# CPLD.net
KiCad netlist of a schematic drawn in Altium Designer
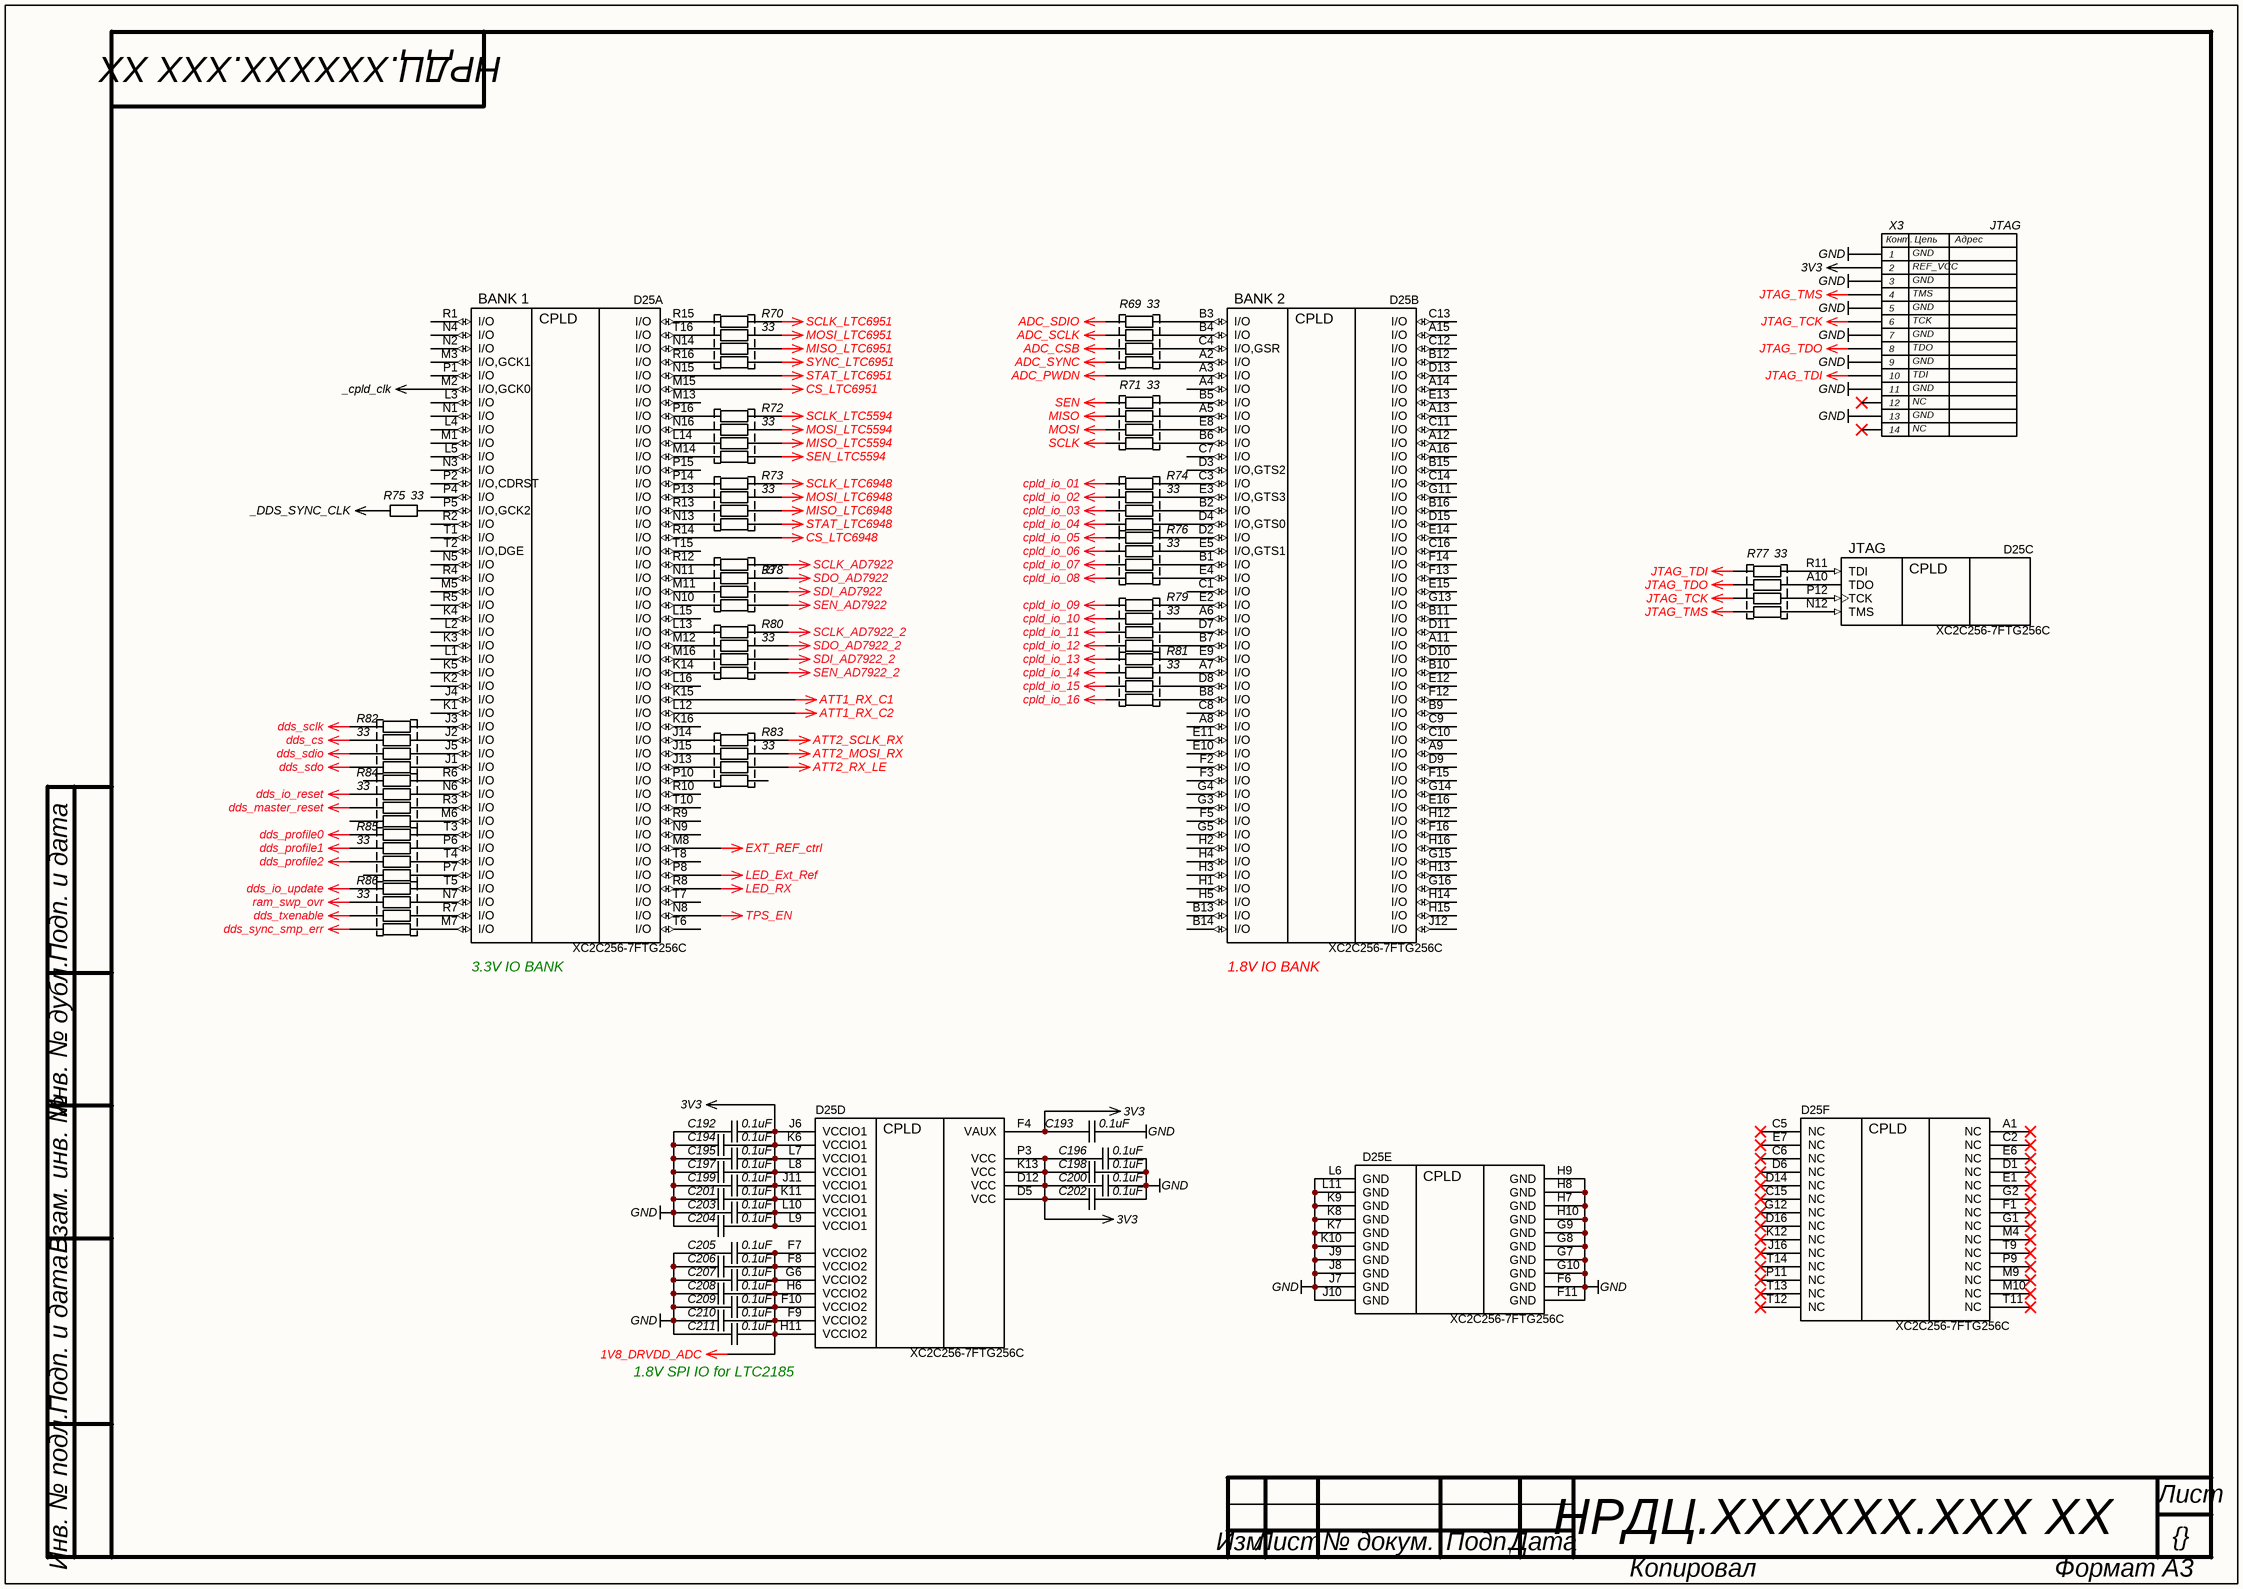
[diagram p0: CPLD.SchDoc]

(export (version "E")
  (design (tool "Eeschema 10.0.6"))
  (components
    (comp (ref "C192")
      (value "0.1uF")
      (footprint "C0402")
      (description "SMD Capacitor")
      (fields (field (name "MANUFACTURER") "Murata") (field (name "TOLERANCE") "10%"))
      (libsource (lib "Kintex_SDR") (part "CAP"))
    )
    (comp (ref "C193")
      (value "0.1uF")
      (footprint "C0402")
      (description "SMD Capacitor")
      (fields (field (name "MANUFACTURER") "Murata") (field (name "TOLERANCE") "10%"))
      (libsource (lib "Kintex_SDR") (part "CAP"))
    )
    (comp (ref "C194")
      (value "0.1uF")
      (footprint "C0402")
      (description "SMD Capacitor")
      (fields (field (name "MANUFACTURER") "Murata") (field (name "TOLERANCE") "10%"))
      (libsource (lib "Kintex_SDR") (part "CAP"))
    )
    (comp (ref "C195")
      (value "0.1uF")
      (footprint "C0402")
      (description "SMD Capacitor")
      (fields (field (name "MANUFACTURER") "Murata") (field (name "TOLERANCE") "10%"))
      (libsource (lib "Kintex_SDR") (part "CAP"))
    )
    (comp (ref "C196")
      (value "0.1uF")
      (footprint "C0402")
      (description "SMD Capacitor")
      (fields (field (name "MANUFACTURER") "Murata") (field (name "TOLERANCE") "10%"))
      (libsource (lib "Kintex_SDR") (part "CAP"))
    )
    (comp (ref "C197")
      (value "0.1uF")
      (footprint "C0402")
      (description "SMD Capacitor")
      (fields (field (name "MANUFACTURER") "Murata") (field (name "TOLERANCE") "10%"))
      (libsource (lib "Kintex_SDR") (part "CAP"))
    )
    (comp (ref "C198")
      (value "0.1uF")
      (footprint "C0402")
      (description "SMD Capacitor")
      (fields (field (name "MANUFACTURER") "Murata") (field (name "TOLERANCE") "10%"))
      (libsource (lib "Kintex_SDR") (part "CAP"))
    )
    (comp (ref "C199")
      (value "0.1uF")
      (footprint "C0402")
      (description "SMD Capacitor")
      (fields (field (name "MANUFACTURER") "Murata") (field (name "TOLERANCE") "10%"))
      (libsource (lib "Kintex_SDR") (part "CAP"))
    )
    (comp (ref "C200")
      (value "0.1uF")
      (footprint "C0402")
      (description "SMD Capacitor")
      (fields (field (name "MANUFACTURER") "Murata") (field (name "TOLERANCE") "10%"))
      (libsource (lib "Kintex_SDR") (part "CAP"))
    )
    (comp (ref "C201")
      (value "0.1uF")
      (footprint "C0402")
      (description "SMD Capacitor")
      (fields (field (name "MANUFACTURER") "Murata") (field (name "TOLERANCE") "10%"))
      (libsource (lib "Kintex_SDR") (part "CAP"))
    )
    (comp (ref "C202")
      (value "0.1uF")
      (footprint "C0402")
      (description "SMD Capacitor")
      (fields (field (name "MANUFACTURER") "Murata") (field (name "TOLERANCE") "10%"))
      (libsource (lib "Kintex_SDR") (part "CAP"))
    )
    (comp (ref "C203")
      (value "0.1uF")
      (footprint "C0402")
      (description "SMD Capacitor")
      (fields (field (name "MANUFACTURER") "Murata") (field (name "TOLERANCE") "10%"))
      (libsource (lib "Kintex_SDR") (part "CAP"))
    )
    (comp (ref "C204")
      (value "0.1uF")
      (footprint "C0402")
      (description "SMD Capacitor")
      (fields (field (name "MANUFACTURER") "Murata") (field (name "TOLERANCE") "10%"))
      (libsource (lib "Kintex_SDR") (part "CAP"))
    )
    (comp (ref "C205")
      (value "0.1uF")
      (footprint "C0402")
      (description "SMD Capacitor")
      (fields (field (name "MANUFACTURER") "Murata") (field (name "TOLERANCE") "10%"))
      (libsource (lib "Kintex_SDR") (part "CAP"))
    )
    (comp (ref "C206")
      (value "0.1uF")
      (footprint "C0402")
      (description "SMD Capacitor")
      (fields (field (name "MANUFACTURER") "Murata") (field (name "TOLERANCE") "10%"))
      (libsource (lib "Kintex_SDR") (part "CAP"))
    )
    (comp (ref "C207")
      (value "0.1uF")
      (footprint "C0402")
      (description "SMD Capacitor")
      (fields (field (name "MANUFACTURER") "Murata") (field (name "TOLERANCE") "10%"))
      (libsource (lib "Kintex_SDR") (part "CAP"))
    )
    (comp (ref "C208")
      (value "0.1uF")
      (footprint "C0402")
      (description "SMD Capacitor")
      (fields (field (name "MANUFACTURER") "Murata") (field (name "TOLERANCE") "10%"))
      (libsource (lib "Kintex_SDR") (part "CAP"))
    )
    (comp (ref "C209")
      (value "0.1uF")
      (footprint "C0402")
      (description "SMD Capacitor")
      (fields (field (name "MANUFACTURER") "Murata") (field (name "TOLERANCE") "10%"))
      (libsource (lib "Kintex_SDR") (part "CAP"))
    )
    (comp (ref "C210")
      (value "0.1uF")
      (footprint "C0402")
      (description "SMD Capacitor")
      (fields (field (name "MANUFACTURER") "Murata") (field (name "TOLERANCE") "10%"))
      (libsource (lib "Kintex_SDR") (part "CAP"))
    )
    (comp (ref "C211")
      (value "0.1uF")
      (footprint "C0402")
      (description "SMD Capacitor")
      (fields (field (name "MANUFACTURER") "Murata") (field (name "TOLERANCE") "10%"))
      (libsource (lib "Kintex_SDR") (part "CAP"))
    )
    (comp (ref "D25")
      (value "XC2C256-7FTG256C")
      (footprint "DBLib:FTG256")
      (description "CoolRunner-II 1.8V, 256 Macrocell CPLD, 184 User I/Os, 256-Ball FTBGA, Commercial Grade, Pb-Free")
      (libsource (lib "DBLib") (part "XC2C256-7FTG256C"))
    )
    (comp (ref "R69")
      (value "33")
      (footprint "EXN8V")
      (description "Chip Resistor Array")
      (fields (field (name "TOLERANCE") "5%") (field (name "MANUFACTURER") "Panasonic"))
      (libsource (lib "Kintex_SDR") (part "RES 4x0402"))
    )
    (comp (ref "R70")
      (value "33")
      (footprint "EXN8V")
      (description "Chip Resistor Array")
      (fields (field (name "TOLERANCE") "5%") (field (name "MANUFACTURER") "Panasonic"))
      (libsource (lib "Kintex_SDR") (part "RES 4x0402"))
    )
    (comp (ref "R71")
      (value "33")
      (footprint "EXN8V")
      (description "Chip Resistor Array")
      (fields (field (name "TOLERANCE") "5%") (field (name "MANUFACTURER") "Panasonic"))
      (libsource (lib "Kintex_SDR") (part "RES 4x0402"))
    )
    (comp (ref "R72")
      (value "33")
      (footprint "EXN8V")
      (description "Chip Resistor Array")
      (fields (field (name "TOLERANCE") "5%") (field (name "MANUFACTURER") "Panasonic"))
      (libsource (lib "Kintex_SDR") (part "RES 4x0402"))
    )
    (comp (ref "R73")
      (value "33")
      (footprint "EXN8V")
      (description "Chip Resistor Array")
      (fields (field (name "TOLERANCE") "5%") (field (name "MANUFACTURER") "Panasonic"))
      (libsource (lib "Kintex_SDR") (part "RES 4x0402"))
    )
    (comp (ref "R74")
      (value "33")
      (footprint "EXN8V")
      (description "Chip Resistor Array")
      (fields (field (name "TOLERANCE") "5%") (field (name "MANUFACTURER") "Panasonic"))
      (libsource (lib "Kintex_SDR") (part "RES 4x0402"))
    )
    (comp (ref "R75")
      (value "33")
      (footprint "R0402")
      (description "SMD Resistor")
      (fields (field (name "POWER") "0.062 Wt") (field (name "TOLERANCE") "5%"))
      (libsource (lib "Kintex_SDR") (part "RES"))
    )
    (comp (ref "R76")
      (value "33")
      (footprint "EXN8V")
      (description "Chip Resistor Array")
      (fields (field (name "TOLERANCE") "5%") (field (name "MANUFACTURER") "Panasonic"))
      (libsource (lib "Kintex_SDR") (part "RES 4x0402"))
    )
    (comp (ref "R77")
      (value "33")
      (footprint "EXN8V")
      (description "Chip Resistor Array")
      (fields (field (name "TOLERANCE") "5%") (field (name "MANUFACTURER") "Panasonic"))
      (libsource (lib "Kintex_SDR") (part "RES 4x0402"))
    )
    (comp (ref "R78")
      (value "33")
      (footprint "EXN8V")
      (description "Chip Resistor Array")
      (fields (field (name "TOLERANCE") "5%") (field (name "MANUFACTURER") "Panasonic"))
      (libsource (lib "Kintex_SDR") (part "RES 4x0402"))
    )
    (comp (ref "R79")
      (value "33")
      (footprint "EXN8V")
      (description "Chip Resistor Array")
      (fields (field (name "TOLERANCE") "5%") (field (name "MANUFACTURER") "Panasonic"))
      (libsource (lib "Kintex_SDR") (part "RES 4x0402"))
    )
    (comp (ref "R80")
      (value "33")
      (footprint "EXN8V")
      (description "Chip Resistor Array")
      (fields (field (name "TOLERANCE") "5%") (field (name "MANUFACTURER") "Panasonic"))
      (libsource (lib "Kintex_SDR") (part "RES 4x0402"))
    )
    (comp (ref "R81")
      (value "33")
      (footprint "EXN8V")
      (description "Chip Resistor Array")
      (fields (field (name "TOLERANCE") "5%") (field (name "MANUFACTURER") "Panasonic"))
      (libsource (lib "Kintex_SDR") (part "RES 4x0402"))
    )
    (comp (ref "R82")
      (value "33")
      (footprint "EXN8V")
      (description "Chip Resistor Array")
      (fields (field (name "TOLERANCE") "5%") (field (name "MANUFACTURER") "Panasonic"))
      (libsource (lib "Kintex_SDR") (part "RES 4x0402"))
    )
    (comp (ref "R83")
      (value "33")
      (footprint "EXN8V")
      (description "Chip Resistor Array")
      (fields (field (name "TOLERANCE") "5%") (field (name "MANUFACTURER") "Panasonic"))
      (libsource (lib "Kintex_SDR") (part "RES 4x0402"))
    )
    (comp (ref "R84")
      (value "33")
      (footprint "EXN8V")
      (description "Chip Resistor Array")
      (fields (field (name "TOLERANCE") "5%") (field (name "MANUFACTURER") "Panasonic"))
      (libsource (lib "Kintex_SDR") (part "RES 4x0402"))
    )
    (comp (ref "R85")
      (value "33")
      (footprint "EXN8V")
      (description "Chip Resistor Array")
      (fields (field (name "TOLERANCE") "5%") (field (name "MANUFACTURER") "Panasonic"))
      (libsource (lib "Kintex_SDR") (part "RES 4x0402"))
    )
    (comp (ref "R86")
      (value "33")
      (footprint "EXN8V")
      (description "Chip Resistor Array")
      (fields (field (name "TOLERANCE") "5%") (field (name "MANUFACTURER") "Panasonic"))
      (libsource (lib "Kintex_SDR") (part "RES 4x0402"))
    )
    (comp (ref "X3")
      (value "JTAG")
      (footprint "DBLib:JTAG Mail 2mm")
      (description "2.00mm Pitch, Milli-Grid PCB Header, Dual Row, Vertical, Through Hole, Shrouded, 14\r\nCircuits")
      (fields (field (name "MANUFACTURER") "Molex"))
      (libsource (lib "DBLib") (part "HDR Debug_14-pin"))
    )
  )
  (nets
    (net (code "1") (name "1V8_DRVDD_ADC") (class "Default")
      (node (ref "C205") (pin "2") (pinfunction "2_2") (pintype "passive"))
      (node (ref "C206") (pin "2") (pinfunction "2_2") (pintype "passive"))
      (node (ref "C207") (pin "2") (pinfunction "2_2") (pintype "passive"))
      (node (ref "C208") (pin "2") (pinfunction "2_2") (pintype "passive"))
      (node (ref "C209") (pin "2") (pinfunction "2_2") (pintype "passive"))
      (node (ref "C210") (pin "2") (pinfunction "2_2") (pintype "passive"))
      (node (ref "C211") (pin "2") (pinfunction "2_2") (pintype "passive"))
      (node (ref "D25") (pin "F10") (pinfunction "VCCIO2_F10") (pintype "power_in"))
      (node (ref "D25") (pin "F7") (pinfunction "VCCIO2_F7") (pintype "power_in"))
      (node (ref "D25") (pin "F8") (pinfunction "VCCIO2_F8") (pintype "power_in"))
      (node (ref "D25") (pin "F9") (pinfunction "VCCIO2_F9") (pintype "power_in"))
      (node (ref "D25") (pin "G6") (pinfunction "VCCIO2_G6") (pintype "power_in"))
      (node (ref "D25") (pin "H11") (pinfunction "VCCIO2_H11") (pintype "power_in"))
      (node (ref "D25") (pin "H6") (pinfunction "VCCIO2_H6") (pintype "power_in"))
    )
    (net (code "2") (name "3V3") (class "Default")
      (node (ref "C192") (pin "2") (pinfunction "2_2") (pintype "passive"))
      (node (ref "C193") (pin "1") (pinfunction "1_1") (pintype "passive"))
      (node (ref "C194") (pin "2") (pinfunction "2_2") (pintype "passive"))
      (node (ref "C195") (pin "2") (pinfunction "2_2") (pintype "passive"))
      (node (ref "C196") (pin "1") (pinfunction "1_1") (pintype "passive"))
      (node (ref "C197") (pin "2") (pinfunction "2_2") (pintype "passive"))
      (node (ref "C198") (pin "1") (pinfunction "1_1") (pintype "passive"))
      (node (ref "C199") (pin "2") (pinfunction "2_2") (pintype "passive"))
      (node (ref "C200") (pin "1") (pinfunction "1_1") (pintype "passive"))
      (node (ref "C201") (pin "2") (pinfunction "2_2") (pintype "passive"))
      (node (ref "C202") (pin "1") (pinfunction "1_1") (pintype "passive"))
      (node (ref "C203") (pin "2") (pinfunction "2_2") (pintype "passive"))
      (node (ref "C204") (pin "2") (pinfunction "2_2") (pintype "passive"))
      (node (ref "D25") (pin "D12") (pinfunction "VCC_D12") (pintype "power_in"))
      (node (ref "D25") (pin "D5") (pinfunction "VCC_D5") (pintype "power_in"))
      (node (ref "D25") (pin "F4") (pinfunction "VAUX_F4") (pintype "power_in"))
      (node (ref "D25") (pin "J11") (pinfunction "VCCIO1_J11") (pintype "power_in"))
      (node (ref "D25") (pin "J6") (pinfunction "VCCIO1_J6") (pintype "power_in"))
      (node (ref "D25") (pin "K11") (pinfunction "VCCIO1_K11") (pintype "power_in"))
      (node (ref "D25") (pin "K13") (pinfunction "VCC_K13") (pintype "power_in"))
      (node (ref "D25") (pin "K6") (pinfunction "VCCIO1_K6") (pintype "power_in"))
      (node (ref "D25") (pin "L10") (pinfunction "VCCIO1_L10") (pintype "power_in"))
      (node (ref "D25") (pin "L7") (pinfunction "VCCIO1_L7") (pintype "power_in"))
      (node (ref "D25") (pin "L8") (pinfunction "VCCIO1_L8") (pintype "power_in"))
      (node (ref "D25") (pin "L9") (pinfunction "VCCIO1_L9") (pintype "power_in"))
      (node (ref "D25") (pin "P3") (pinfunction "VCC_P3") (pintype "power_in"))
      (node (ref "X3") (pin "2") (pinfunction "2_2") (pintype "passive"))
    )
    (net (code "3") (name "ADC_CSB") (class "Default")
      (node (ref "R69") (pin "7") (pinfunction "7_7") (pintype "passive"))
    )
    (net (code "4") (name "ADC_PWDN") (class "Default")
      (node (ref "D25") (pin "A3") (pinfunction "I/O_A3") (pintype "bidirectional"))
    )
    (net (code "5") (name "ADC_SCLK") (class "Default")
      (node (ref "R69") (pin "6") (pinfunction "6_6") (pintype "passive"))
    )
    (net (code "6") (name "ADC_SDIO") (class "Default")
      (node (ref "R69") (pin "5") (pinfunction "5_5") (pintype "passive"))
    )
    (net (code "7") (name "ADC_SYNC") (class "Default")
      (node (ref "R69") (pin "8") (pinfunction "8_8") (pintype "passive"))
    )
    (net (code "8") (name "ATT1_RX_C1") (class "Default")
      (node (ref "D25") (pin "K15") (pinfunction "I/O_K15") (pintype "bidirectional"))
    )
    (net (code "9") (name "ATT1_RX_C2") (class "Default")
      (node (ref "D25") (pin "L12") (pinfunction "I/O_L12") (pintype "bidirectional"))
    )
    (net (code "10") (name "ATT2_MOSI_RX") (class "Default")
      (node (ref "R83") (pin "3") (pinfunction "3_3") (pintype "passive"))
    )
    (net (code "11") (name "ATT2_RX_LE") (class "Default")
      (node (ref "R83") (pin "2") (pinfunction "2_2") (pintype "passive"))
    )
    (net (code "12") (name "ATT2_SCLK_RX") (class "Default")
      (node (ref "R83") (pin "4") (pinfunction "4_4") (pintype "passive"))
    )
    (net (code "13") (name "CS_LTC6948") (class "Default")
      (node (ref "D25") (pin "R14") (pinfunction "I/O_R14") (pintype "bidirectional"))
    )
    (net (code "14") (name "CS_LTC6951") (class "Default")
      (node (ref "D25") (pin "M15") (pinfunction "I/O_M15") (pintype "bidirectional"))
    )
    (net (code "15") (name "EXT_REF_ctrl") (class "Default")
      (node (ref "D25") (pin "M8") (pinfunction "I/O_M8") (pintype "bidirectional"))
    )
    (net (code "16") (name "GND") (class "Default")
      (node (ref "C192") (pin "1") (pinfunction "1_1") (pintype "passive"))
      (node (ref "C193") (pin "2") (pinfunction "2_2") (pintype "passive"))
      (node (ref "C194") (pin "1") (pinfunction "1_1") (pintype "passive"))
      (node (ref "C195") (pin "1") (pinfunction "1_1") (pintype "passive"))
      (node (ref "C196") (pin "2") (pinfunction "2_2") (pintype "passive"))
      (node (ref "C197") (pin "1") (pinfunction "1_1") (pintype "passive"))
      (node (ref "C198") (pin "2") (pinfunction "2_2") (pintype "passive"))
      (node (ref "C199") (pin "1") (pinfunction "1_1") (pintype "passive"))
      (node (ref "C200") (pin "2") (pinfunction "2_2") (pintype "passive"))
      (node (ref "C201") (pin "1") (pinfunction "1_1") (pintype "passive"))
      (node (ref "C202") (pin "2") (pinfunction "2_2") (pintype "passive"))
      (node (ref "C203") (pin "1") (pinfunction "1_1") (pintype "passive"))
      (node (ref "C204") (pin "1") (pinfunction "1_1") (pintype "passive"))
      (node (ref "C205") (pin "1") (pinfunction "1_1") (pintype "passive"))
      (node (ref "C206") (pin "1") (pinfunction "1_1") (pintype "passive"))
      (node (ref "C207") (pin "1") (pinfunction "1_1") (pintype "passive"))
      (node (ref "C208") (pin "1") (pinfunction "1_1") (pintype "passive"))
      (node (ref "C209") (pin "1") (pinfunction "1_1") (pintype "passive"))
      (node (ref "C210") (pin "1") (pinfunction "1_1") (pintype "passive"))
      (node (ref "C211") (pin "1") (pinfunction "1_1") (pintype "passive"))
      (node (ref "D25") (pin "F11") (pinfunction "GND_F11") (pintype "power_in"))
      (node (ref "D25") (pin "F6") (pinfunction "GND_F6") (pintype "power_in"))
      (node (ref "D25") (pin "G10") (pinfunction "GND_G10") (pintype "power_in"))
      (node (ref "D25") (pin "G7") (pinfunction "GND_G7") (pintype "power_in"))
      (node (ref "D25") (pin "G8") (pinfunction "GND_G8") (pintype "power_in"))
      (node (ref "D25") (pin "G9") (pinfunction "GND_G9") (pintype "power_in"))
      (node (ref "D25") (pin "H10") (pinfunction "GND_H10") (pintype "power_in"))
      (node (ref "D25") (pin "H7") (pinfunction "GND_H7") (pintype "power_in"))
      (node (ref "D25") (pin "H8") (pinfunction "GND_H8") (pintype "power_in"))
      (node (ref "D25") (pin "H9") (pinfunction "GND_H9") (pintype "power_in"))
      (node (ref "D25") (pin "J10") (pinfunction "GND_J10") (pintype "power_in"))
      (node (ref "D25") (pin "J7") (pinfunction "GND_J7") (pintype "power_in"))
      (node (ref "D25") (pin "J8") (pinfunction "GND_J8") (pintype "power_in"))
      (node (ref "D25") (pin "J9") (pinfunction "GND_J9") (pintype "power_in"))
      (node (ref "D25") (pin "K10") (pinfunction "GND_K10") (pintype "power_in"))
      (node (ref "D25") (pin "K7") (pinfunction "GND_K7") (pintype "power_in"))
      (node (ref "D25") (pin "K8") (pinfunction "GND_K8") (pintype "power_in"))
      (node (ref "D25") (pin "K9") (pinfunction "GND_K9") (pintype "power_in"))
      (node (ref "D25") (pin "L11") (pinfunction "GND_L11") (pintype "power_in"))
      (node (ref "D25") (pin "L6") (pinfunction "GND_L6") (pintype "power_in"))
      (node (ref "X3") (pin "1") (pinfunction "1_1") (pintype "passive"))
      (node (ref "X3") (pin "11") (pinfunction "11_11") (pintype "passive"))
      (node (ref "X3") (pin "13") (pinfunction "13_13") (pintype "passive"))
      (node (ref "X3") (pin "3") (pinfunction "3_3") (pintype "passive"))
      (node (ref "X3") (pin "5") (pinfunction "5_5") (pintype "passive"))
      (node (ref "X3") (pin "7") (pinfunction "7_7") (pintype "passive"))
      (node (ref "X3") (pin "9") (pinfunction "9_9") (pintype "passive"))
    )
    (net (code "17") (name "JTAG_TCK") (class "Default")
      (node (ref "R77") (pin "7") (pinfunction "7_7") (pintype "passive"))
      (node (ref "X3") (pin "6") (pinfunction "6_6") (pintype "passive"))
    )
    (net (code "18") (name "JTAG_TDI") (class "Default")
      (node (ref "R77") (pin "5") (pinfunction "5_5") (pintype "passive"))
      (node (ref "X3") (pin "10") (pinfunction "10_10") (pintype "passive"))
    )
    (net (code "19") (name "JTAG_TDO") (class "Default")
      (node (ref "R77") (pin "6") (pinfunction "6_6") (pintype "passive"))
      (node (ref "X3") (pin "8") (pinfunction "8_8") (pintype "passive"))
    )
    (net (code "20") (name "JTAG_TMS") (class "Default")
      (node (ref "R77") (pin "8") (pinfunction "8_8") (pintype "passive"))
      (node (ref "X3") (pin "4") (pinfunction "4_4") (pintype "passive"))
    )
    (net (code "21") (name "LED_Ext_Ref") (class "Default")
      (node (ref "D25") (pin "P8") (pinfunction "I/O_P8") (pintype "bidirectional"))
    )
    (net (code "22") (name "LED_RX") (class "Default")
      (node (ref "D25") (pin "R8") (pinfunction "I/O_R8") (pintype "bidirectional"))
    )
    (net (code "23") (name "MISO") (class "Default")
      (node (ref "R71") (pin "6") (pinfunction "6_6") (pintype "passive"))
    )
    (net (code "24") (name "MISO_LTC5594") (class "Default")
      (node (ref "R72") (pin "2") (pinfunction "2_2") (pintype "passive"))
    )
    (net (code "25") (name "MISO_LTC6948") (class "Default")
      (node (ref "R73") (pin "2") (pinfunction "2_2") (pintype "passive"))
    )
    (net (code "26") (name "MISO_LTC6951") (class "Default")
      (node (ref "R70") (pin "2") (pinfunction "2_2") (pintype "passive"))
    )
    (net (code "27") (name "MOSI") (class "Default")
      (node (ref "R71") (pin "7") (pinfunction "7_7") (pintype "passive"))
    )
    (net (code "28") (name "MOSI_LTC5594") (class "Default")
      (node (ref "R72") (pin "3") (pinfunction "3_3") (pintype "passive"))
    )
    (net (code "29") (name "MOSI_LTC6948") (class "Default")
      (node (ref "R73") (pin "3") (pinfunction "3_3") (pintype "passive"))
    )
    (net (code "30") (name "MOSI_LTC6951") (class "Default")
      (node (ref "R70") (pin "3") (pinfunction "3_3") (pintype "passive"))
    )
    (net (code "31") (name "Net-(D25A-I{slash}O,GCK2)") (class "Default")
      (node (ref "D25") (pin "P5") (pinfunction "I/O,GCK2_P5") (pintype "bidirectional"))
      (node (ref "R75") (pin "2") (pinfunction "2_2") (pintype "passive"))
    )
    (net (code "32") (name "Net-(D25A-I{slash}O-PadJ1)") (class "Default")
      (node (ref "D25") (pin "J1") (pinfunction "I/O_J1") (pintype "bidirectional"))
      (node (ref "R82") (pin "1") (pinfunction "1_1") (pintype "passive"))
    )
    (net (code "33") (name "Net-(D25A-I{slash}O-PadJ2)") (class "Default")
      (node (ref "D25") (pin "J2") (pinfunction "I/O_J2") (pintype "bidirectional"))
      (node (ref "R82") (pin "3") (pinfunction "3_3") (pintype "passive"))
    )
    (net (code "34") (name "Net-(D25A-I{slash}O-PadJ3)") (class "Default")
      (node (ref "D25") (pin "J3") (pinfunction "I/O_J3") (pintype "bidirectional"))
      (node (ref "R82") (pin "4") (pinfunction "4_4") (pintype "passive"))
    )
    (net (code "35") (name "Net-(D25A-I{slash}O-PadJ5)") (class "Default")
      (node (ref "D25") (pin "J5") (pinfunction "I/O_J5") (pintype "bidirectional"))
      (node (ref "R82") (pin "2") (pinfunction "2_2") (pintype "passive"))
    )
    (net (code "36") (name "Net-(D25A-I{slash}O-PadJ13)") (class "Default")
      (node (ref "D25") (pin "J13") (pinfunction "I/O_J13") (pintype "bidirectional"))
      (node (ref "R83") (pin "7") (pinfunction "7_7") (pintype "passive"))
    )
    (net (code "37") (name "Net-(D25A-I{slash}O-PadJ14)") (class "Default")
      (node (ref "D25") (pin "J14") (pinfunction "I/O_J14") (pintype "bidirectional"))
      (node (ref "R83") (pin "5") (pinfunction "5_5") (pintype "passive"))
    )
    (net (code "38") (name "Net-(D25A-I{slash}O-PadJ15)") (class "Default")
      (node (ref "D25") (pin "J15") (pinfunction "I/O_J15") (pintype "bidirectional"))
      (node (ref "R83") (pin "6") (pinfunction "6_6") (pintype "passive"))
    )
    (net (code "39") (name "Net-(D25A-I{slash}O-PadK14)") (class "Default")
      (node (ref "D25") (pin "K14") (pinfunction "I/O_K14") (pintype "bidirectional"))
      (node (ref "R80") (pin "8") (pinfunction "8_8") (pintype "passive"))
    )
    (net (code "40") (name "Net-(D25A-I{slash}O-PadL13)") (class "Default")
      (node (ref "D25") (pin "L13") (pinfunction "I/O_L13") (pintype "bidirectional"))
      (node (ref "R80") (pin "5") (pinfunction "5_5") (pintype "passive"))
    )
    (net (code "41") (name "Net-(D25A-I{slash}O-PadL14)") (class "Default")
      (node (ref "D25") (pin "L14") (pinfunction "I/O_L14") (pintype "bidirectional"))
      (node (ref "R72") (pin "7") (pinfunction "7_7") (pintype "passive"))
    )
    (net (code "42") (name "Net-(D25A-I{slash}O-PadM6)") (class "Default")
      (node (ref "D25") (pin "M6") (pinfunction "I/O_M6") (pintype "bidirectional"))
      (node (ref "R84") (pin "1") (pinfunction "1_1") (pintype "passive"))
    )
    (net (code "43") (name "Net-(D25A-I{slash}O-PadM7)") (class "Default")
      (node (ref "D25") (pin "M7") (pinfunction "I/O_M7") (pintype "bidirectional"))
      (node (ref "R86") (pin "1") (pinfunction "1_1") (pintype "passive"))
    )
    (net (code "44") (name "Net-(D25A-I{slash}O-PadM11)") (class "Default")
      (node (ref "D25") (pin "M11") (pinfunction "I/O_M11") (pintype "bidirectional"))
      (node (ref "R78") (pin "7") (pinfunction "7_7") (pintype "passive"))
    )
    (net (code "45") (name "Net-(D25A-I{slash}O-PadM12)") (class "Default")
      (node (ref "D25") (pin "M12") (pinfunction "I/O_M12") (pintype "bidirectional"))
      (node (ref "R80") (pin "6") (pinfunction "6_6") (pintype "passive"))
    )
    (net (code "46") (name "Net-(D25A-I{slash}O-PadM14)") (class "Default")
      (node (ref "D25") (pin "M14") (pinfunction "I/O_M14") (pintype "bidirectional"))
      (node (ref "R72") (pin "8") (pinfunction "8_8") (pintype "passive"))
    )
    (net (code "47") (name "Net-(D25A-I{slash}O-PadM16)") (class "Default")
      (node (ref "D25") (pin "M16") (pinfunction "I/O_M16") (pintype "bidirectional"))
      (node (ref "R80") (pin "7") (pinfunction "7_7") (pintype "passive"))
    )
    (net (code "48") (name "Net-(D25A-I{slash}O-PadN6)") (class "Default")
      (node (ref "D25") (pin "N6") (pinfunction "I/O_N6") (pintype "bidirectional"))
      (node (ref "R84") (pin "3") (pinfunction "3_3") (pintype "passive"))
    )
    (net (code "49") (name "Net-(D25A-I{slash}O-PadN7)") (class "Default")
      (node (ref "D25") (pin "N7") (pinfunction "I/O_N7") (pintype "bidirectional"))
      (node (ref "R86") (pin "3") (pinfunction "3_3") (pintype "passive"))
    )
    (net (code "50") (name "Net-(D25A-I{slash}O-PadN10)") (class "Default")
      (node (ref "D25") (pin "N10") (pinfunction "I/O_N10") (pintype "bidirectional"))
      (node (ref "R78") (pin "8") (pinfunction "8_8") (pintype "passive"))
    )
    (net (code "51") (name "Net-(D25A-I{slash}O-PadN11)") (class "Default")
      (node (ref "D25") (pin "N11") (pinfunction "I/O_N11") (pintype "bidirectional"))
      (node (ref "R78") (pin "6") (pinfunction "6_6") (pintype "passive"))
    )
    (net (code "52") (name "Net-(D25A-I{slash}O-PadN13)") (class "Default")
      (node (ref "D25") (pin "N13") (pinfunction "I/O_N13") (pintype "bidirectional"))
      (node (ref "R73") (pin "8") (pinfunction "8_8") (pintype "passive"))
    )
    (net (code "53") (name "Net-(D25A-I{slash}O-PadN14)") (class "Default")
      (node (ref "D25") (pin "N14") (pinfunction "I/O_N14") (pintype "bidirectional"))
      (node (ref "R70") (pin "7") (pinfunction "7_7") (pintype "passive"))
    )
    (net (code "54") (name "Net-(D25A-I{slash}O-PadN16)") (class "Default")
      (node (ref "D25") (pin "N16") (pinfunction "I/O_N16") (pintype "bidirectional"))
      (node (ref "R72") (pin "6") (pinfunction "6_6") (pintype "passive"))
    )
    (net (code "55") (name "Net-(D25A-I{slash}O-PadP6)") (class "Default")
      (node (ref "D25") (pin "P6") (pinfunction "I/O_P6") (pintype "bidirectional"))
      (node (ref "R85") (pin "3") (pinfunction "3_3") (pintype "passive"))
    )
    (net (code "56") (name "Net-(D25A-I{slash}O-PadP7)") (class "Default")
      (node (ref "D25") (pin "P7") (pinfunction "I/O_P7") (pintype "bidirectional"))
      (node (ref "R85") (pin "1") (pinfunction "1_1") (pintype "passive"))
    )
    (net (code "57") (name "Net-(D25A-I{slash}O-PadP10)") (class "Default")
      (node (ref "D25") (pin "P10") (pinfunction "I/O_P10") (pintype "bidirectional"))
      (node (ref "R83") (pin "8") (pinfunction "8_8") (pintype "passive"))
    )
    (net (code "58") (name "Net-(D25A-I{slash}O-PadP13)") (class "Default")
      (node (ref "D25") (pin "P13") (pinfunction "I/O_P13") (pintype "bidirectional"))
      (node (ref "R73") (pin "6") (pinfunction "6_6") (pintype "passive"))
    )
    (net (code "59") (name "Net-(D25A-I{slash}O-PadP14)") (class "Default")
      (node (ref "D25") (pin "P14") (pinfunction "I/O_P14") (pintype "bidirectional"))
      (node (ref "R73") (pin "5") (pinfunction "5_5") (pintype "passive"))
    )
    (net (code "60") (name "Net-(D25A-I{slash}O-PadP16)") (class "Default")
      (node (ref "D25") (pin "P16") (pinfunction "I/O_P16") (pintype "bidirectional"))
      (node (ref "R72") (pin "5") (pinfunction "5_5") (pintype "passive"))
    )
    (net (code "61") (name "Net-(D25A-I{slash}O-PadR3)") (class "Default")
      (node (ref "D25") (pin "R3") (pinfunction "I/O_R3") (pintype "bidirectional"))
      (node (ref "R84") (pin "2") (pinfunction "2_2") (pintype "passive"))
    )
    (net (code "62") (name "Net-(D25A-I{slash}O-PadR6)") (class "Default")
      (node (ref "D25") (pin "R6") (pinfunction "I/O_R6") (pintype "bidirectional"))
      (node (ref "R84") (pin "4") (pinfunction "4_4") (pintype "passive"))
    )
    (net (code "63") (name "Net-(D25A-I{slash}O-PadR7)") (class "Default")
      (node (ref "D25") (pin "R7") (pinfunction "I/O_R7") (pintype "bidirectional"))
      (node (ref "R86") (pin "2") (pinfunction "2_2") (pintype "passive"))
    )
    (net (code "64") (name "Net-(D25A-I{slash}O-PadR12)") (class "Default")
      (node (ref "D25") (pin "R12") (pinfunction "I/O_R12") (pintype "bidirectional"))
      (node (ref "R78") (pin "5") (pinfunction "5_5") (pintype "passive"))
    )
    (net (code "65") (name "Net-(D25A-I{slash}O-PadR13)") (class "Default")
      (node (ref "D25") (pin "R13") (pinfunction "I/O_R13") (pintype "bidirectional"))
      (node (ref "R73") (pin "7") (pinfunction "7_7") (pintype "passive"))
    )
    (net (code "66") (name "Net-(D25A-I{slash}O-PadR15)") (class "Default")
      (node (ref "D25") (pin "R15") (pinfunction "I/O_R15") (pintype "bidirectional"))
      (node (ref "R70") (pin "5") (pinfunction "5_5") (pintype "passive"))
    )
    (net (code "67") (name "Net-(D25A-I{slash}O-PadR16)") (class "Default")
      (node (ref "D25") (pin "R16") (pinfunction "I/O_R16") (pintype "bidirectional"))
      (node (ref "R70") (pin "8") (pinfunction "8_8") (pintype "passive"))
    )
    (net (code "68") (name "Net-(D25A-I{slash}O-PadT3)") (class "Default")
      (node (ref "D25") (pin "T3") (pinfunction "I/O_T3") (pintype "bidirectional"))
      (node (ref "R85") (pin "4") (pinfunction "4_4") (pintype "passive"))
    )
    (net (code "69") (name "Net-(D25A-I{slash}O-PadT4)") (class "Default")
      (node (ref "D25") (pin "T4") (pinfunction "I/O_T4") (pintype "bidirectional"))
      (node (ref "R85") (pin "2") (pinfunction "2_2") (pintype "passive"))
    )
    (net (code "70") (name "Net-(D25A-I{slash}O-PadT5)") (class "Default")
      (node (ref "D25") (pin "T5") (pinfunction "I/O_T5") (pintype "bidirectional"))
      (node (ref "R86") (pin "4") (pinfunction "4_4") (pintype "passive"))
    )
    (net (code "71") (name "Net-(D25A-I{slash}O-PadT16)") (class "Default")
      (node (ref "D25") (pin "T16") (pinfunction "I/O_T16") (pintype "bidirectional"))
      (node (ref "R70") (pin "6") (pinfunction "6_6") (pintype "passive"))
    )
    (net (code "72") (name "Net-(D25B-I{slash}O,GSR)") (class "Default")
      (node (ref "D25") (pin "C4") (pinfunction "I/O,GSR_C4") (pintype "bidirectional"))
      (node (ref "R69") (pin "2") (pinfunction "2_2") (pintype "passive"))
    )
    (net (code "73") (name "Net-(D25B-I{slash}O,GTS0)") (class "Default")
      (node (ref "D25") (pin "D4") (pinfunction "I/O,GTS0_D4") (pintype "bidirectional"))
      (node (ref "R74") (pin "1") (pinfunction "1_1") (pintype "passive"))
    )
    (net (code "74") (name "Net-(D25B-I{slash}O,GTS1)") (class "Default")
      (node (ref "D25") (pin "E5") (pinfunction "I/O,GTS1_E5") (pintype "bidirectional"))
      (node (ref "R76") (pin "3") (pinfunction "3_3") (pintype "passive"))
    )
    (net (code "75") (name "Net-(D25B-I{slash}O,GTS3)") (class "Default")
      (node (ref "D25") (pin "E3") (pinfunction "I/O,GTS3_E3") (pintype "bidirectional"))
      (node (ref "R74") (pin "3") (pinfunction "3_3") (pintype "passive"))
    )
    (net (code "76") (name "Net-(D25B-I{slash}O-PadA2)") (class "Default")
      (node (ref "D25") (pin "A2") (pinfunction "I/O_A2") (pintype "bidirectional"))
      (node (ref "R69") (pin "1") (pinfunction "1_1") (pintype "passive"))
    )
    (net (code "77") (name "Net-(D25B-I{slash}O-PadA5)") (class "Default")
      (node (ref "D25") (pin "A5") (pinfunction "I/O_A5") (pintype "bidirectional"))
      (node (ref "R71") (pin "3") (pinfunction "3_3") (pintype "passive"))
    )
    (net (code "78") (name "Net-(D25B-I{slash}O-PadA6)") (class "Default")
      (node (ref "D25") (pin "A6") (pinfunction "I/O_A6") (pintype "bidirectional"))
      (node (ref "R79") (pin "3") (pinfunction "3_3") (pintype "passive"))
    )
    (net (code "79") (name "Net-(D25B-I{slash}O-PadA7)") (class "Default")
      (node (ref "D25") (pin "A7") (pinfunction "I/O_A7") (pintype "bidirectional"))
      (node (ref "R81") (pin "3") (pinfunction "3_3") (pintype "passive"))
    )
    (net (code "80") (name "Net-(D25B-I{slash}O-PadB1)") (class "Default")
      (node (ref "D25") (pin "B1") (pinfunction "I/O_B1") (pintype "bidirectional"))
      (node (ref "R76") (pin "2") (pinfunction "2_2") (pintype "passive"))
    )
    (net (code "81") (name "Net-(D25B-I{slash}O-PadB2)") (class "Default")
      (node (ref "D25") (pin "B2") (pinfunction "I/O_B2") (pintype "bidirectional"))
      (node (ref "R74") (pin "2") (pinfunction "2_2") (pintype "passive"))
    )
    (net (code "82") (name "Net-(D25B-I{slash}O-PadB3)") (class "Default")
      (node (ref "D25") (pin "B3") (pinfunction "I/O_B3") (pintype "bidirectional"))
      (node (ref "R69") (pin "4") (pinfunction "4_4") (pintype "passive"))
    )
    (net (code "83") (name "Net-(D25B-I{slash}O-PadB4)") (class "Default")
      (node (ref "D25") (pin "B4") (pinfunction "I/O_B4") (pintype "bidirectional"))
      (node (ref "R69") (pin "3") (pinfunction "3_3") (pintype "passive"))
    )
    (net (code "84") (name "Net-(D25B-I{slash}O-PadB5)") (class "Default")
      (node (ref "D25") (pin "B5") (pinfunction "I/O_B5") (pintype "bidirectional"))
      (node (ref "R71") (pin "4") (pinfunction "4_4") (pintype "passive"))
    )
    (net (code "85") (name "Net-(D25B-I{slash}O-PadB6)") (class "Default")
      (node (ref "D25") (pin "B6") (pinfunction "I/O_B6") (pintype "bidirectional"))
      (node (ref "R71") (pin "1") (pinfunction "1_1") (pintype "passive"))
    )
    (net (code "86") (name "Net-(D25B-I{slash}O-PadB7)") (class "Default")
      (node (ref "D25") (pin "B7") (pinfunction "I/O_B7") (pintype "bidirectional"))
      (node (ref "R79") (pin "1") (pinfunction "1_1") (pintype "passive"))
    )
    (net (code "87") (name "Net-(D25B-I{slash}O-PadB8)") (class "Default")
      (node (ref "D25") (pin "B8") (pinfunction "I/O_B8") (pintype "bidirectional"))
      (node (ref "R81") (pin "1") (pinfunction "1_1") (pintype "passive"))
    )
    (net (code "88") (name "Net-(D25B-I{slash}O-PadC3)") (class "Default")
      (node (ref "D25") (pin "C3") (pinfunction "I/O_C3") (pintype "bidirectional"))
      (node (ref "R74") (pin "4") (pinfunction "4_4") (pintype "passive"))
    )
    (net (code "89") (name "Net-(D25B-I{slash}O-PadD2)") (class "Default")
      (node (ref "D25") (pin "D2") (pinfunction "I/O_D2") (pintype "bidirectional"))
      (node (ref "R76") (pin "4") (pinfunction "4_4") (pintype "passive"))
    )
    (net (code "90") (name "Net-(D25B-I{slash}O-PadD7)") (class "Default")
      (node (ref "D25") (pin "D7") (pinfunction "I/O_D7") (pintype "bidirectional"))
      (node (ref "R79") (pin "2") (pinfunction "2_2") (pintype "passive"))
    )
    (net (code "91") (name "Net-(D25B-I{slash}O-PadD8)") (class "Default")
      (node (ref "D25") (pin "D8") (pinfunction "I/O_D8") (pintype "bidirectional"))
      (node (ref "R81") (pin "2") (pinfunction "2_2") (pintype "passive"))
    )
    (net (code "92") (name "Net-(D25B-I{slash}O-PadE2)") (class "Default")
      (node (ref "D25") (pin "E2") (pinfunction "I/O_E2") (pintype "bidirectional"))
      (node (ref "R79") (pin "4") (pinfunction "4_4") (pintype "passive"))
    )
    (net (code "93") (name "Net-(D25B-I{slash}O-PadE4)") (class "Default")
      (node (ref "D25") (pin "E4") (pinfunction "I/O_E4") (pintype "bidirectional"))
      (node (ref "R76") (pin "1") (pinfunction "1_1") (pintype "passive"))
    )
    (net (code "94") (name "Net-(D25B-I{slash}O-PadE8)") (class "Default")
      (node (ref "D25") (pin "E8") (pinfunction "I/O_E8") (pintype "bidirectional"))
      (node (ref "R71") (pin "2") (pinfunction "2_2") (pintype "passive"))
    )
    (net (code "95") (name "Net-(D25B-I{slash}O-PadE9)") (class "Default")
      (node (ref "D25") (pin "E9") (pinfunction "I/O_E9") (pintype "bidirectional"))
      (node (ref "R81") (pin "4") (pinfunction "4_4") (pintype "passive"))
    )
    (net (code "96") (name "Net-(D25C-TCK)") (class "Default")
      (node (ref "D25") (pin "P12") (pinfunction "TCK_P12") (pintype "input"))
      (node (ref "R77") (pin "2") (pinfunction "2_2") (pintype "passive"))
    )
    (net (code "97") (name "Net-(D25C-TDI)") (class "Default")
      (node (ref "D25") (pin "R11") (pinfunction "TDI_R11") (pintype "input"))
      (node (ref "R77") (pin "4") (pinfunction "4_4") (pintype "passive"))
    )
    (net (code "98") (name "Net-(D25C-TDO)") (class "Default")
      (node (ref "D25") (pin "A10") (pinfunction "TDO_A10") (pintype "passive"))
      (node (ref "R77") (pin "3") (pinfunction "3_3") (pintype "passive"))
    )
    (net (code "99") (name "Net-(D25C-TMS)") (class "Default")
      (node (ref "D25") (pin "N12") (pinfunction "TMS_N12") (pintype "input"))
      (node (ref "R77") (pin "1") (pinfunction "1_1") (pintype "passive"))
    )
    (net (code "100") (name "SCLK") (class "Default")
      (node (ref "R71") (pin "8") (pinfunction "8_8") (pintype "passive"))
    )
    (net (code "101") (name "SCLK_AD7922") (class "Default")
      (node (ref "R78") (pin "4") (pinfunction "4_4") (pintype "passive"))
    )
    (net (code "102") (name "SCLK_AD7922_2") (class "Default")
      (node (ref "R80") (pin "4") (pinfunction "4_4") (pintype "passive"))
    )
    (net (code "103") (name "SCLK_LTC5594") (class "Default")
      (node (ref "R72") (pin "4") (pinfunction "4_4") (pintype "passive"))
    )
    (net (code "104") (name "SCLK_LTC6948") (class "Default")
      (node (ref "R73") (pin "4") (pinfunction "4_4") (pintype "passive"))
    )
    (net (code "105") (name "SCLK_LTC6951") (class "Default")
      (node (ref "R70") (pin "4") (pinfunction "4_4") (pintype "passive"))
    )
    (net (code "106") (name "SDI_AD7922") (class "Default")
      (node (ref "R78") (pin "2") (pinfunction "2_2") (pintype "passive"))
    )
    (net (code "107") (name "SDI_AD7922_2") (class "Default")
      (node (ref "R80") (pin "2") (pinfunction "2_2") (pintype "passive"))
    )
    (net (code "108") (name "SDO_AD7922") (class "Default")
      (node (ref "R78") (pin "3") (pinfunction "3_3") (pintype "passive"))
    )
    (net (code "109") (name "SDO_AD7922_2") (class "Default")
      (node (ref "R80") (pin "3") (pinfunction "3_3") (pintype "passive"))
    )
    (net (code "110") (name "SEN") (class "Default")
      (node (ref "R71") (pin "5") (pinfunction "5_5") (pintype "passive"))
    )
    (net (code "111") (name "SEN_AD7922") (class "Default")
      (node (ref "R78") (pin "1") (pinfunction "1_1") (pintype "passive"))
    )
    (net (code "112") (name "SEN_AD7922_2") (class "Default")
      (node (ref "R80") (pin "1") (pinfunction "1_1") (pintype "passive"))
    )
    (net (code "113") (name "SEN_LTC5594") (class "Default")
      (node (ref "R72") (pin "1") (pinfunction "1_1") (pintype "passive"))
    )
    (net (code "114") (name "STAT_LTC6948") (class "Default")
      (node (ref "R73") (pin "1") (pinfunction "1_1") (pintype "passive"))
    )
    (net (code "115") (name "STAT_LTC6951") (class "Default")
      (node (ref "D25") (pin "N15") (pinfunction "I/O_N15") (pintype "bidirectional"))
    )
    (net (code "116") (name "SYNC_LTC6951") (class "Default")
      (node (ref "R70") (pin "1") (pinfunction "1_1") (pintype "passive"))
    )
    (net (code "117") (name "TPS_EN") (class "Default")
      (node (ref "D25") (pin "N8") (pinfunction "I/O_N8") (pintype "bidirectional"))
    )
    (net (code "118") (name "_DDS_SYNC_CLK") (class "Default")
      (node (ref "R75") (pin "1") (pinfunction "1_1") (pintype "passive"))
    )
    (net (code "119") (name "_cpld_clk") (class "Default")
      (node (ref "D25") (pin "M2") (pinfunction "I/O,GCK0_M2") (pintype "bidirectional"))
    )
    (net (code "120") (name "cpld_io_01") (class "Default")
      (node (ref "R74") (pin "5") (pinfunction "5_5") (pintype "passive"))
    )
    (net (code "121") (name "cpld_io_02") (class "Default")
      (node (ref "R74") (pin "6") (pinfunction "6_6") (pintype "passive"))
    )
    (net (code "122") (name "cpld_io_03") (class "Default")
      (node (ref "R74") (pin "7") (pinfunction "7_7") (pintype "passive"))
    )
    (net (code "123") (name "cpld_io_04") (class "Default")
      (node (ref "R74") (pin "8") (pinfunction "8_8") (pintype "passive"))
    )
    (net (code "124") (name "cpld_io_05") (class "Default")
      (node (ref "R76") (pin "5") (pinfunction "5_5") (pintype "passive"))
    )
    (net (code "125") (name "cpld_io_06") (class "Default")
      (node (ref "R76") (pin "6") (pinfunction "6_6") (pintype "passive"))
    )
    (net (code "126") (name "cpld_io_07") (class "Default")
      (node (ref "R76") (pin "7") (pinfunction "7_7") (pintype "passive"))
    )
    (net (code "127") (name "cpld_io_08") (class "Default")
      (node (ref "R76") (pin "8") (pinfunction "8_8") (pintype "passive"))
    )
    (net (code "128") (name "cpld_io_09") (class "Default")
      (node (ref "R79") (pin "5") (pinfunction "5_5") (pintype "passive"))
    )
    (net (code "129") (name "cpld_io_10") (class "Default")
      (node (ref "R79") (pin "6") (pinfunction "6_6") (pintype "passive"))
    )
    (net (code "130") (name "cpld_io_11") (class "Default")
      (node (ref "R79") (pin "7") (pinfunction "7_7") (pintype "passive"))
    )
    (net (code "131") (name "cpld_io_12") (class "Default")
      (node (ref "R79") (pin "8") (pinfunction "8_8") (pintype "passive"))
    )
    (net (code "132") (name "cpld_io_13") (class "Default")
      (node (ref "R81") (pin "5") (pinfunction "5_5") (pintype "passive"))
    )
    (net (code "133") (name "cpld_io_14") (class "Default")
      (node (ref "R81") (pin "6") (pinfunction "6_6") (pintype "passive"))
    )
    (net (code "134") (name "cpld_io_15") (class "Default")
      (node (ref "R81") (pin "7") (pinfunction "7_7") (pintype "passive"))
    )
    (net (code "135") (name "cpld_io_16") (class "Default")
      (node (ref "R81") (pin "8") (pinfunction "8_8") (pintype "passive"))
    )
    (net (code "136") (name "dds_cs") (class "Default")
      (node (ref "R82") (pin "6") (pinfunction "6_6") (pintype "passive"))
    )
    (net (code "137") (name "dds_io_reset") (class "Default")
      (node (ref "R84") (pin "6") (pinfunction "6_6") (pintype "passive"))
    )
    (net (code "138") (name "dds_io_update") (class "Default")
      (node (ref "R86") (pin "5") (pinfunction "5_5") (pintype "passive"))
    )
    (net (code "139") (name "dds_master_reset") (class "Default")
      (node (ref "R84") (pin "7") (pinfunction "7_7") (pintype "passive"))
    )
    (net (code "140") (name "dds_profile0") (class "Default")
      (node (ref "R85") (pin "5") (pinfunction "5_5") (pintype "passive"))
    )
    (net (code "141") (name "dds_profile1") (class "Default")
      (node (ref "R85") (pin "6") (pinfunction "6_6") (pintype "passive"))
    )
    (net (code "142") (name "dds_profile2") (class "Default")
      (node (ref "R85") (pin "7") (pinfunction "7_7") (pintype "passive"))
    )
    (net (code "143") (name "dds_sclk") (class "Default")
      (node (ref "R82") (pin "5") (pinfunction "5_5") (pintype "passive"))
    )
    (net (code "144") (name "dds_sdio") (class "Default")
      (node (ref "R82") (pin "7") (pinfunction "7_7") (pintype "passive"))
    )
    (net (code "145") (name "dds_sdo") (class "Default")
      (node (ref "R82") (pin "8") (pinfunction "8_8") (pintype "passive"))
    )
    (net (code "146") (name "dds_sync_smp_err") (class "Default")
      (node (ref "R86") (pin "8") (pinfunction "8_8") (pintype "passive"))
    )
    (net (code "147") (name "dds_txenable") (class "Default")
      (node (ref "R86") (pin "7") (pinfunction "7_7") (pintype "passive"))
    )
    (net (code "148") (name "ram_swp_ovr") (class "Default")
      (node (ref "R86") (pin "6") (pinfunction "6_6") (pintype "passive"))
    )
    (net (code "149") (name "unconnected-(D25A-I{slash}O,CDRST-PadP2)") (class "Default")
      (node (ref "D25") (pin "P2") (pinfunction "I/O,CDRST_P2") (pintype "bidirectional"))
    )
    (net (code "150") (name "unconnected-(D25A-I{slash}O,DGE-PadT2)") (class "Default")
      (node (ref "D25") (pin "T2") (pinfunction "I/O,DGE_T2") (pintype "bidirectional"))
    )
    (net (code "151") (name "unconnected-(D25A-I{slash}O,GCK1-PadM3)") (class "Default")
      (node (ref "D25") (pin "M3") (pinfunction "I/O,GCK1_M3") (pintype "bidirectional"))
    )
    (net (code "152") (name "unconnected-(D25A-I{slash}O-PadJ4)") (class "Default")
      (node (ref "D25") (pin "J4") (pinfunction "I/O_J4") (pintype "bidirectional"))
    )
    (net (code "153") (name "unconnected-(D25A-I{slash}O-PadK1)") (class "Default")
      (node (ref "D25") (pin "K1") (pinfunction "I/O_K1") (pintype "bidirectional"))
    )
    (net (code "154") (name "unconnected-(D25A-I{slash}O-PadK2)") (class "Default")
      (node (ref "D25") (pin "K2") (pinfunction "I/O_K2") (pintype "bidirectional"))
    )
    (net (code "155") (name "unconnected-(D25A-I{slash}O-PadK3)") (class "Default")
      (node (ref "D25") (pin "K3") (pinfunction "I/O_K3") (pintype "bidirectional"))
    )
    (net (code "156") (name "unconnected-(D25A-I{slash}O-PadK4)") (class "Default")
      (node (ref "D25") (pin "K4") (pinfunction "I/O_K4") (pintype "bidirectional"))
    )
    (net (code "157") (name "unconnected-(D25A-I{slash}O-PadK5)") (class "Default")
      (node (ref "D25") (pin "K5") (pinfunction "I/O_K5") (pintype "bidirectional"))
    )
    (net (code "158") (name "unconnected-(D25A-I{slash}O-PadK16)") (class "Default")
      (node (ref "D25") (pin "K16") (pinfunction "I/O_K16") (pintype "bidirectional"))
    )
    (net (code "159") (name "unconnected-(D25A-I{slash}O-PadL1)") (class "Default")
      (node (ref "D25") (pin "L1") (pinfunction "I/O_L1") (pintype "bidirectional"))
    )
    (net (code "160") (name "unconnected-(D25A-I{slash}O-PadL2)") (class "Default")
      (node (ref "D25") (pin "L2") (pinfunction "I/O_L2") (pintype "bidirectional"))
    )
    (net (code "161") (name "unconnected-(D25A-I{slash}O-PadL3)") (class "Default")
      (node (ref "D25") (pin "L3") (pinfunction "I/O_L3") (pintype "bidirectional"))
    )
    (net (code "162") (name "unconnected-(D25A-I{slash}O-PadL4)") (class "Default")
      (node (ref "D25") (pin "L4") (pinfunction "I/O_L4") (pintype "bidirectional"))
    )
    (net (code "163") (name "unconnected-(D25A-I{slash}O-PadL5)") (class "Default")
      (node (ref "D25") (pin "L5") (pinfunction "I/O_L5") (pintype "bidirectional"))
    )
    (net (code "164") (name "unconnected-(D25A-I{slash}O-PadL15)") (class "Default")
      (node (ref "D25") (pin "L15") (pinfunction "I/O_L15") (pintype "bidirectional"))
    )
    (net (code "165") (name "unconnected-(D25A-I{slash}O-PadL16)") (class "Default")
      (node (ref "D25") (pin "L16") (pinfunction "I/O_L16") (pintype "bidirectional"))
    )
    (net (code "166") (name "unconnected-(D25A-I{slash}O-PadM1)") (class "Default")
      (node (ref "D25") (pin "M1") (pinfunction "I/O_M1") (pintype "bidirectional"))
    )
    (net (code "167") (name "unconnected-(D25A-I{slash}O-PadM5)") (class "Default")
      (node (ref "D25") (pin "M5") (pinfunction "I/O_M5") (pintype "bidirectional"))
    )
    (net (code "168") (name "unconnected-(D25A-I{slash}O-PadM13)") (class "Default")
      (node (ref "D25") (pin "M13") (pinfunction "I/O_M13") (pintype "bidirectional"))
    )
    (net (code "169") (name "unconnected-(D25A-I{slash}O-PadN1)") (class "Default")
      (node (ref "D25") (pin "N1") (pinfunction "I/O_N1") (pintype "bidirectional"))
    )
    (net (code "170") (name "unconnected-(D25A-I{slash}O-PadN2)") (class "Default")
      (node (ref "D25") (pin "N2") (pinfunction "I/O_N2") (pintype "bidirectional"))
    )
    (net (code "171") (name "unconnected-(D25A-I{slash}O-PadN3)") (class "Default")
      (node (ref "D25") (pin "N3") (pinfunction "I/O_N3") (pintype "bidirectional"))
    )
    (net (code "172") (name "unconnected-(D25A-I{slash}O-PadN4)") (class "Default")
      (node (ref "D25") (pin "N4") (pinfunction "I/O_N4") (pintype "bidirectional"))
    )
    (net (code "173") (name "unconnected-(D25A-I{slash}O-PadN5)") (class "Default")
      (node (ref "D25") (pin "N5") (pinfunction "I/O_N5") (pintype "bidirectional"))
    )
    (net (code "174") (name "unconnected-(D25A-I{slash}O-PadN9)") (class "Default")
      (node (ref "D25") (pin "N9") (pinfunction "I/O_N9") (pintype "bidirectional"))
    )
    (net (code "175") (name "unconnected-(D25A-I{slash}O-PadP1)") (class "Default")
      (node (ref "D25") (pin "P1") (pinfunction "I/O_P1") (pintype "bidirectional"))
    )
    (net (code "176") (name "unconnected-(D25A-I{slash}O-PadP4)") (class "Default")
      (node (ref "D25") (pin "P4") (pinfunction "I/O_P4") (pintype "bidirectional"))
    )
    (net (code "177") (name "unconnected-(D25A-I{slash}O-PadP15)") (class "Default")
      (node (ref "D25") (pin "P15") (pinfunction "I/O_P15") (pintype "bidirectional"))
    )
    (net (code "178") (name "unconnected-(D25A-I{slash}O-PadR1)") (class "Default")
      (node (ref "D25") (pin "R1") (pinfunction "I/O_R1") (pintype "bidirectional"))
    )
    (net (code "179") (name "unconnected-(D25A-I{slash}O-PadR2)") (class "Default")
      (node (ref "D25") (pin "R2") (pinfunction "I/O_R2") (pintype "bidirectional"))
    )
    (net (code "180") (name "unconnected-(D25A-I{slash}O-PadR4)") (class "Default")
      (node (ref "D25") (pin "R4") (pinfunction "I/O_R4") (pintype "bidirectional"))
    )
    (net (code "181") (name "unconnected-(D25A-I{slash}O-PadR5)") (class "Default")
      (node (ref "D25") (pin "R5") (pinfunction "I/O_R5") (pintype "bidirectional"))
    )
    (net (code "182") (name "unconnected-(D25A-I{slash}O-PadR9)") (class "Default")
      (node (ref "D25") (pin "R9") (pinfunction "I/O_R9") (pintype "bidirectional"))
    )
    (net (code "183") (name "unconnected-(D25A-I{slash}O-PadR10)") (class "Default")
      (node (ref "D25") (pin "R10") (pinfunction "I/O_R10") (pintype "bidirectional"))
    )
    (net (code "184") (name "unconnected-(D25A-I{slash}O-PadT1)") (class "Default")
      (node (ref "D25") (pin "T1") (pinfunction "I/O_T1") (pintype "bidirectional"))
    )
    (net (code "185") (name "unconnected-(D25A-I{slash}O-PadT6)") (class "Default")
      (node (ref "D25") (pin "T6") (pinfunction "I/O_T6") (pintype "bidirectional"))
    )
    (net (code "186") (name "unconnected-(D25A-I{slash}O-PadT7)") (class "Default")
      (node (ref "D25") (pin "T7") (pinfunction "I/O_T7") (pintype "bidirectional"))
    )
    (net (code "187") (name "unconnected-(D25A-I{slash}O-PadT8)") (class "Default")
      (node (ref "D25") (pin "T8") (pinfunction "I/O_T8") (pintype "bidirectional"))
    )
    (net (code "188") (name "unconnected-(D25A-I{slash}O-PadT10)") (class "Default")
      (node (ref "D25") (pin "T10") (pinfunction "I/O_T10") (pintype "bidirectional"))
    )
    (net (code "189") (name "unconnected-(D25A-I{slash}O-PadT15)") (class "Default")
      (node (ref "D25") (pin "T15") (pinfunction "I/O_T15") (pintype "bidirectional"))
    )
    (net (code "190") (name "unconnected-(D25B-I{slash}O,GTS2-PadD3)") (class "Default")
      (node (ref "D25") (pin "D3") (pinfunction "I/O,GTS2_D3") (pintype "bidirectional"))
    )
    (net (code "191") (name "unconnected-(D25B-I{slash}O-PadA4)") (class "Default")
      (node (ref "D25") (pin "A4") (pinfunction "I/O_A4") (pintype "bidirectional"))
    )
    (net (code "192") (name "unconnected-(D25B-I{slash}O-PadA8)") (class "Default")
      (node (ref "D25") (pin "A8") (pinfunction "I/O_A8") (pintype "bidirectional"))
    )
    (net (code "193") (name "unconnected-(D25B-I{slash}O-PadA9)") (class "Default")
      (node (ref "D25") (pin "A9") (pinfunction "I/O_A9") (pintype "bidirectional"))
    )
    (net (code "194") (name "unconnected-(D25B-I{slash}O-PadA11)") (class "Default")
      (node (ref "D25") (pin "A11") (pinfunction "I/O_A11") (pintype "bidirectional"))
    )
    (net (code "195") (name "unconnected-(D25B-I{slash}O-PadA12)") (class "Default")
      (node (ref "D25") (pin "A12") (pinfunction "I/O_A12") (pintype "bidirectional"))
    )
    (net (code "196") (name "unconnected-(D25B-I{slash}O-PadA13)") (class "Default")
      (node (ref "D25") (pin "A13") (pinfunction "I/O_A13") (pintype "bidirectional"))
    )
    (net (code "197") (name "unconnected-(D25B-I{slash}O-PadA14)") (class "Default")
      (node (ref "D25") (pin "A14") (pinfunction "I/O_A14") (pintype "bidirectional"))
    )
    (net (code "198") (name "unconnected-(D25B-I{slash}O-PadA15)") (class "Default")
      (node (ref "D25") (pin "A15") (pinfunction "I/O_A15") (pintype "bidirectional"))
    )
    (net (code "199") (name "unconnected-(D25B-I{slash}O-PadA16)") (class "Default")
      (node (ref "D25") (pin "A16") (pinfunction "I/O_A16") (pintype "bidirectional"))
    )
    (net (code "200") (name "unconnected-(D25B-I{slash}O-PadB9)") (class "Default")
      (node (ref "D25") (pin "B9") (pinfunction "I/O_B9") (pintype "bidirectional"))
    )
    (net (code "201") (name "unconnected-(D25B-I{slash}O-PadB10)") (class "Default")
      (node (ref "D25") (pin "B10") (pinfunction "I/O_B10") (pintype "bidirectional"))
    )
    (net (code "202") (name "unconnected-(D25B-I{slash}O-PadB11)") (class "Default")
      (node (ref "D25") (pin "B11") (pinfunction "I/O_B11") (pintype "bidirectional"))
    )
    (net (code "203") (name "unconnected-(D25B-I{slash}O-PadB12)") (class "Default")
      (node (ref "D25") (pin "B12") (pinfunction "I/O_B12") (pintype "bidirectional"))
    )
    (net (code "204") (name "unconnected-(D25B-I{slash}O-PadB13)") (class "Default")
      (node (ref "D25") (pin "B13") (pinfunction "I/O_B13") (pintype "bidirectional"))
    )
    (net (code "205") (name "unconnected-(D25B-I{slash}O-PadB14)") (class "Default")
      (node (ref "D25") (pin "B14") (pinfunction "I/O_B14") (pintype "bidirectional"))
    )
    (net (code "206") (name "unconnected-(D25B-I{slash}O-PadB15)") (class "Default")
      (node (ref "D25") (pin "B15") (pinfunction "I/O_B15") (pintype "bidirectional"))
    )
    (net (code "207") (name "unconnected-(D25B-I{slash}O-PadB16)") (class "Default")
      (node (ref "D25") (pin "B16") (pinfunction "I/O_B16") (pintype "bidirectional"))
    )
    (net (code "208") (name "unconnected-(D25B-I{slash}O-PadC1)") (class "Default")
      (node (ref "D25") (pin "C1") (pinfunction "I/O_C1") (pintype "bidirectional"))
    )
    (net (code "209") (name "unconnected-(D25B-I{slash}O-PadC7)") (class "Default")
      (node (ref "D25") (pin "C7") (pinfunction "I/O_C7") (pintype "bidirectional"))
    )
    (net (code "210") (name "unconnected-(D25B-I{slash}O-PadC8)") (class "Default")
      (node (ref "D25") (pin "C8") (pinfunction "I/O_C8") (pintype "bidirectional"))
    )
    (net (code "211") (name "unconnected-(D25B-I{slash}O-PadC9)") (class "Default")
      (node (ref "D25") (pin "C9") (pinfunction "I/O_C9") (pintype "bidirectional"))
    )
    (net (code "212") (name "unconnected-(D25B-I{slash}O-PadC10)") (class "Default")
      (node (ref "D25") (pin "C10") (pinfunction "I/O_C10") (pintype "bidirectional"))
    )
    (net (code "213") (name "unconnected-(D25B-I{slash}O-PadC11)") (class "Default")
      (node (ref "D25") (pin "C11") (pinfunction "I/O_C11") (pintype "bidirectional"))
    )
    (net (code "214") (name "unconnected-(D25B-I{slash}O-PadC12)") (class "Default")
      (node (ref "D25") (pin "C12") (pinfunction "I/O_C12") (pintype "bidirectional"))
    )
    (net (code "215") (name "unconnected-(D25B-I{slash}O-PadC13)") (class "Default")
      (node (ref "D25") (pin "C13") (pinfunction "I/O_C13") (pintype "bidirectional"))
    )
    (net (code "216") (name "unconnected-(D25B-I{slash}O-PadC14)") (class "Default")
      (node (ref "D25") (pin "C14") (pinfunction "I/O_C14") (pintype "bidirectional"))
    )
    (net (code "217") (name "unconnected-(D25B-I{slash}O-PadC16)") (class "Default")
      (node (ref "D25") (pin "C16") (pinfunction "I/O_C16") (pintype "bidirectional"))
    )
    (net (code "218") (name "unconnected-(D25B-I{slash}O-PadD9)") (class "Default")
      (node (ref "D25") (pin "D9") (pinfunction "I/O_D9") (pintype "bidirectional"))
    )
    (net (code "219") (name "unconnected-(D25B-I{slash}O-PadD10)") (class "Default")
      (node (ref "D25") (pin "D10") (pinfunction "I/O_D10") (pintype "bidirectional"))
    )
    (net (code "220") (name "unconnected-(D25B-I{slash}O-PadD11)") (class "Default")
      (node (ref "D25") (pin "D11") (pinfunction "I/O_D11") (pintype "bidirectional"))
    )
    (net (code "221") (name "unconnected-(D25B-I{slash}O-PadD13)") (class "Default")
      (node (ref "D25") (pin "D13") (pinfunction "I/O_D13") (pintype "bidirectional"))
    )
    (net (code "222") (name "unconnected-(D25B-I{slash}O-PadD15)") (class "Default")
      (node (ref "D25") (pin "D15") (pinfunction "I/O_D15") (pintype "bidirectional"))
    )
    (net (code "223") (name "unconnected-(D25B-I{slash}O-PadE10)") (class "Default")
      (node (ref "D25") (pin "E10") (pinfunction "I/O_E10") (pintype "bidirectional"))
    )
    (net (code "224") (name "unconnected-(D25B-I{slash}O-PadE11)") (class "Default")
      (node (ref "D25") (pin "E11") (pinfunction "I/O_E11") (pintype "bidirectional"))
    )
    (net (code "225") (name "unconnected-(D25B-I{slash}O-PadE12)") (class "Default")
      (node (ref "D25") (pin "E12") (pinfunction "I/O_E12") (pintype "bidirectional"))
    )
    (net (code "226") (name "unconnected-(D25B-I{slash}O-PadE13)") (class "Default")
      (node (ref "D25") (pin "E13") (pinfunction "I/O_E13") (pintype "bidirectional"))
    )
    (net (code "227") (name "unconnected-(D25B-I{slash}O-PadE14)") (class "Default")
      (node (ref "D25") (pin "E14") (pinfunction "I/O_E14") (pintype "bidirectional"))
    )
    (net (code "228") (name "unconnected-(D25B-I{slash}O-PadE15)") (class "Default")
      (node (ref "D25") (pin "E15") (pinfunction "I/O_E15") (pintype "bidirectional"))
    )
    (net (code "229") (name "unconnected-(D25B-I{slash}O-PadE16)") (class "Default")
      (node (ref "D25") (pin "E16") (pinfunction "I/O_E16") (pintype "bidirectional"))
    )
    (net (code "230") (name "unconnected-(D25B-I{slash}O-PadF2)") (class "Default")
      (node (ref "D25") (pin "F2") (pinfunction "I/O_F2") (pintype "bidirectional"))
    )
    (net (code "231") (name "unconnected-(D25B-I{slash}O-PadF3)") (class "Default")
      (node (ref "D25") (pin "F3") (pinfunction "I/O_F3") (pintype "bidirectional"))
    )
    (net (code "232") (name "unconnected-(D25B-I{slash}O-PadF5)") (class "Default")
      (node (ref "D25") (pin "F5") (pinfunction "I/O_F5") (pintype "bidirectional"))
    )
    (net (code "233") (name "unconnected-(D25B-I{slash}O-PadF12)") (class "Default")
      (node (ref "D25") (pin "F12") (pinfunction "I/O_F12") (pintype "bidirectional"))
    )
    (net (code "234") (name "unconnected-(D25B-I{slash}O-PadF13)") (class "Default")
      (node (ref "D25") (pin "F13") (pinfunction "I/O_F13") (pintype "bidirectional"))
    )
    (net (code "235") (name "unconnected-(D25B-I{slash}O-PadF14)") (class "Default")
      (node (ref "D25") (pin "F14") (pinfunction "I/O_F14") (pintype "bidirectional"))
    )
    (net (code "236") (name "unconnected-(D25B-I{slash}O-PadF15)") (class "Default")
      (node (ref "D25") (pin "F15") (pinfunction "I/O_F15") (pintype "bidirectional"))
    )
    (net (code "237") (name "unconnected-(D25B-I{slash}O-PadF16)") (class "Default")
      (node (ref "D25") (pin "F16") (pinfunction "I/O_F16") (pintype "bidirectional"))
    )
    (net (code "238") (name "unconnected-(D25B-I{slash}O-PadG3)") (class "Default")
      (node (ref "D25") (pin "G3") (pinfunction "I/O_G3") (pintype "bidirectional"))
    )
    (net (code "239") (name "unconnected-(D25B-I{slash}O-PadG4)") (class "Default")
      (node (ref "D25") (pin "G4") (pinfunction "I/O_G4") (pintype "bidirectional"))
    )
    (net (code "240") (name "unconnected-(D25B-I{slash}O-PadG5)") (class "Default")
      (node (ref "D25") (pin "G5") (pinfunction "I/O_G5") (pintype "bidirectional"))
    )
    (net (code "241") (name "unconnected-(D25B-I{slash}O-PadG11)") (class "Default")
      (node (ref "D25") (pin "G11") (pinfunction "I/O_G11") (pintype "bidirectional"))
    )
    (net (code "242") (name "unconnected-(D25B-I{slash}O-PadG13)") (class "Default")
      (node (ref "D25") (pin "G13") (pinfunction "I/O_G13") (pintype "bidirectional"))
    )
    (net (code "243") (name "unconnected-(D25B-I{slash}O-PadG14)") (class "Default")
      (node (ref "D25") (pin "G14") (pinfunction "I/O_G14") (pintype "bidirectional"))
    )
    (net (code "244") (name "unconnected-(D25B-I{slash}O-PadG15)") (class "Default")
      (node (ref "D25") (pin "G15") (pinfunction "I/O_G15") (pintype "bidirectional"))
    )
    (net (code "245") (name "unconnected-(D25B-I{slash}O-PadG16)") (class "Default")
      (node (ref "D25") (pin "G16") (pinfunction "I/O_G16") (pintype "bidirectional"))
    )
    (net (code "246") (name "unconnected-(D25B-I{slash}O-PadH1)") (class "Default")
      (node (ref "D25") (pin "H1") (pinfunction "I/O_H1") (pintype "bidirectional"))
    )
    (net (code "247") (name "unconnected-(D25B-I{slash}O-PadH2)") (class "Default")
      (node (ref "D25") (pin "H2") (pinfunction "I/O_H2") (pintype "bidirectional"))
    )
    (net (code "248") (name "unconnected-(D25B-I{slash}O-PadH3)") (class "Default")
      (node (ref "D25") (pin "H3") (pinfunction "I/O_H3") (pintype "bidirectional"))
    )
    (net (code "249") (name "unconnected-(D25B-I{slash}O-PadH4)") (class "Default")
      (node (ref "D25") (pin "H4") (pinfunction "I/O_H4") (pintype "bidirectional"))
    )
    (net (code "250") (name "unconnected-(D25B-I{slash}O-PadH5)") (class "Default")
      (node (ref "D25") (pin "H5") (pinfunction "I/O_H5") (pintype "bidirectional"))
    )
    (net (code "251") (name "unconnected-(D25B-I{slash}O-PadH12)") (class "Default")
      (node (ref "D25") (pin "H12") (pinfunction "I/O_H12") (pintype "bidirectional"))
    )
    (net (code "252") (name "unconnected-(D25B-I{slash}O-PadH13)") (class "Default")
      (node (ref "D25") (pin "H13") (pinfunction "I/O_H13") (pintype "bidirectional"))
    )
    (net (code "253") (name "unconnected-(D25B-I{slash}O-PadH14)") (class "Default")
      (node (ref "D25") (pin "H14") (pinfunction "I/O_H14") (pintype "bidirectional"))
    )
    (net (code "254") (name "unconnected-(D25B-I{slash}O-PadH15)") (class "Default")
      (node (ref "D25") (pin "H15") (pinfunction "I/O_H15") (pintype "bidirectional"))
    )
    (net (code "255") (name "unconnected-(D25B-I{slash}O-PadH16)") (class "Default")
      (node (ref "D25") (pin "H16") (pinfunction "I/O_H16") (pintype "bidirectional"))
    )
    (net (code "256") (name "unconnected-(D25B-I{slash}O-PadJ12)") (class "Default")
      (node (ref "D25") (pin "J12") (pinfunction "I/O_J12") (pintype "bidirectional"))
    )
    (net (code "257") (name "unconnected-(D25F-NC-PadA1)") (class "Default")
      (node (ref "D25") (pin "A1") (pinfunction "NC_A1") (pintype "passive+no_connect"))
    )
    (net (code "258") (name "unconnected-(D25F-NC-PadC2)") (class "Default")
      (node (ref "D25") (pin "C2") (pinfunction "NC_C2") (pintype "passive+no_connect"))
    )
    (net (code "259") (name "unconnected-(D25F-NC-PadC5)") (class "Default")
      (node (ref "D25") (pin "C5") (pinfunction "NC_C5") (pintype "passive+no_connect"))
    )
    (net (code "260") (name "unconnected-(D25F-NC-PadC6)") (class "Default")
      (node (ref "D25") (pin "C6") (pinfunction "NC_C6") (pintype "passive+no_connect"))
    )
    (net (code "261") (name "unconnected-(D25F-NC-PadC15)") (class "Default")
      (node (ref "D25") (pin "C15") (pinfunction "NC_C15") (pintype "passive+no_connect"))
    )
    (net (code "262") (name "unconnected-(D25F-NC-PadD1)") (class "Default")
      (node (ref "D25") (pin "D1") (pinfunction "NC_D1") (pintype "passive+no_connect"))
    )
    (net (code "263") (name "unconnected-(D25F-NC-PadD6)") (class "Default")
      (node (ref "D25") (pin "D6") (pinfunction "NC_D6") (pintype "passive+no_connect"))
    )
    (net (code "264") (name "unconnected-(D25F-NC-PadD14)") (class "Default")
      (node (ref "D25") (pin "D14") (pinfunction "NC_D14") (pintype "passive+no_connect"))
    )
    (net (code "265") (name "unconnected-(D25F-NC-PadD16)") (class "Default")
      (node (ref "D25") (pin "D16") (pinfunction "NC_D16") (pintype "passive+no_connect"))
    )
    (net (code "266") (name "unconnected-(D25F-NC-PadE1)") (class "Default")
      (node (ref "D25") (pin "E1") (pinfunction "NC_E1") (pintype "passive+no_connect"))
    )
    (net (code "267") (name "unconnected-(D25F-NC-PadE6)") (class "Default")
      (node (ref "D25") (pin "E6") (pinfunction "NC_E6") (pintype "passive+no_connect"))
    )
    (net (code "268") (name "unconnected-(D25F-NC-PadE7)") (class "Default")
      (node (ref "D25") (pin "E7") (pinfunction "NC_E7") (pintype "passive+no_connect"))
    )
    (net (code "269") (name "unconnected-(D25F-NC-PadF1)") (class "Default")
      (node (ref "D25") (pin "F1") (pinfunction "NC_F1") (pintype "passive+no_connect"))
    )
    (net (code "270") (name "unconnected-(D25F-NC-PadG1)") (class "Default")
      (node (ref "D25") (pin "G1") (pinfunction "NC_G1") (pintype "passive+no_connect"))
    )
    (net (code "271") (name "unconnected-(D25F-NC-PadG2)") (class "Default")
      (node (ref "D25") (pin "G2") (pinfunction "NC_G2") (pintype "passive+no_connect"))
    )
    (net (code "272") (name "unconnected-(D25F-NC-PadG12)") (class "Default")
      (node (ref "D25") (pin "G12") (pinfunction "NC_G12") (pintype "passive+no_connect"))
    )
    (net (code "273") (name "unconnected-(D25F-NC-PadJ16)") (class "Default")
      (node (ref "D25") (pin "J16") (pinfunction "NC_J16") (pintype "passive+no_connect"))
    )
    (net (code "274") (name "unconnected-(D25F-NC-PadK12)") (class "Default")
      (node (ref "D25") (pin "K12") (pinfunction "NC_K12") (pintype "passive+no_connect"))
    )
    (net (code "275") (name "unconnected-(D25F-NC-PadM4)") (class "Default")
      (node (ref "D25") (pin "M4") (pinfunction "NC_M4") (pintype "passive+no_connect"))
    )
    (net (code "276") (name "unconnected-(D25F-NC-PadM9)") (class "Default")
      (node (ref "D25") (pin "M9") (pinfunction "NC_M9") (pintype "passive+no_connect"))
    )
    (net (code "277") (name "unconnected-(D25F-NC-PadM10)") (class "Default")
      (node (ref "D25") (pin "M10") (pinfunction "NC_M10") (pintype "passive+no_connect"))
    )
    (net (code "278") (name "unconnected-(D25F-NC-PadP9)") (class "Default")
      (node (ref "D25") (pin "P9") (pinfunction "NC_P9") (pintype "passive+no_connect"))
    )
    (net (code "279") (name "unconnected-(D25F-NC-PadP11)") (class "Default")
      (node (ref "D25") (pin "P11") (pinfunction "NC_P11") (pintype "passive+no_connect"))
    )
    (net (code "280") (name "unconnected-(D25F-NC-PadT9)") (class "Default")
      (node (ref "D25") (pin "T9") (pinfunction "NC_T9") (pintype "passive+no_connect"))
    )
    (net (code "281") (name "unconnected-(D25F-NC-PadT11)") (class "Default")
      (node (ref "D25") (pin "T11") (pinfunction "NC_T11") (pintype "passive+no_connect"))
    )
    (net (code "282") (name "unconnected-(D25F-NC-PadT12)") (class "Default")
      (node (ref "D25") (pin "T12") (pinfunction "NC_T12") (pintype "passive+no_connect"))
    )
    (net (code "283") (name "unconnected-(D25F-NC-PadT13)") (class "Default")
      (node (ref "D25") (pin "T13") (pinfunction "NC_T13") (pintype "passive+no_connect"))
    )
    (net (code "284") (name "unconnected-(D25F-NC-PadT14)") (class "Default")
      (node (ref "D25") (pin "T14") (pinfunction "NC_T14") (pintype "passive+no_connect"))
    )
    (net (code "285") (name "unconnected-(R83-Pad1)") (class "Default")
      (node (ref "R83") (pin "1") (pinfunction "1_1") (pintype "passive"))
    )
    (net (code "286") (name "unconnected-(R84-Pad5)") (class "Default")
      (node (ref "R84") (pin "5") (pinfunction "5_5") (pintype "passive"))
    )
    (net (code "287") (name "unconnected-(R84-Pad8)") (class "Default")
      (node (ref "R84") (pin "8") (pinfunction "8_8") (pintype "passive"))
    )
    (net (code "288") (name "unconnected-(R85-Pad8)") (class "Default")
      (node (ref "R85") (pin "8") (pinfunction "8_8") (pintype "passive"))
    )
    (net (code "289") (name "unconnected-(X3-Pad12)") (class "Default")
      (node (ref "X3") (pin "12") (pinfunction "12_12") (pintype "passive+no_connect"))
    )
    (net (code "290") (name "unconnected-(X3-Pad14)") (class "Default")
      (node (ref "X3") (pin "14") (pinfunction "14_14") (pintype "passive+no_connect"))
    )
  )
)
